# mikroe-adapter.net
KiCad netlist of a schematic drawn in EAGLE
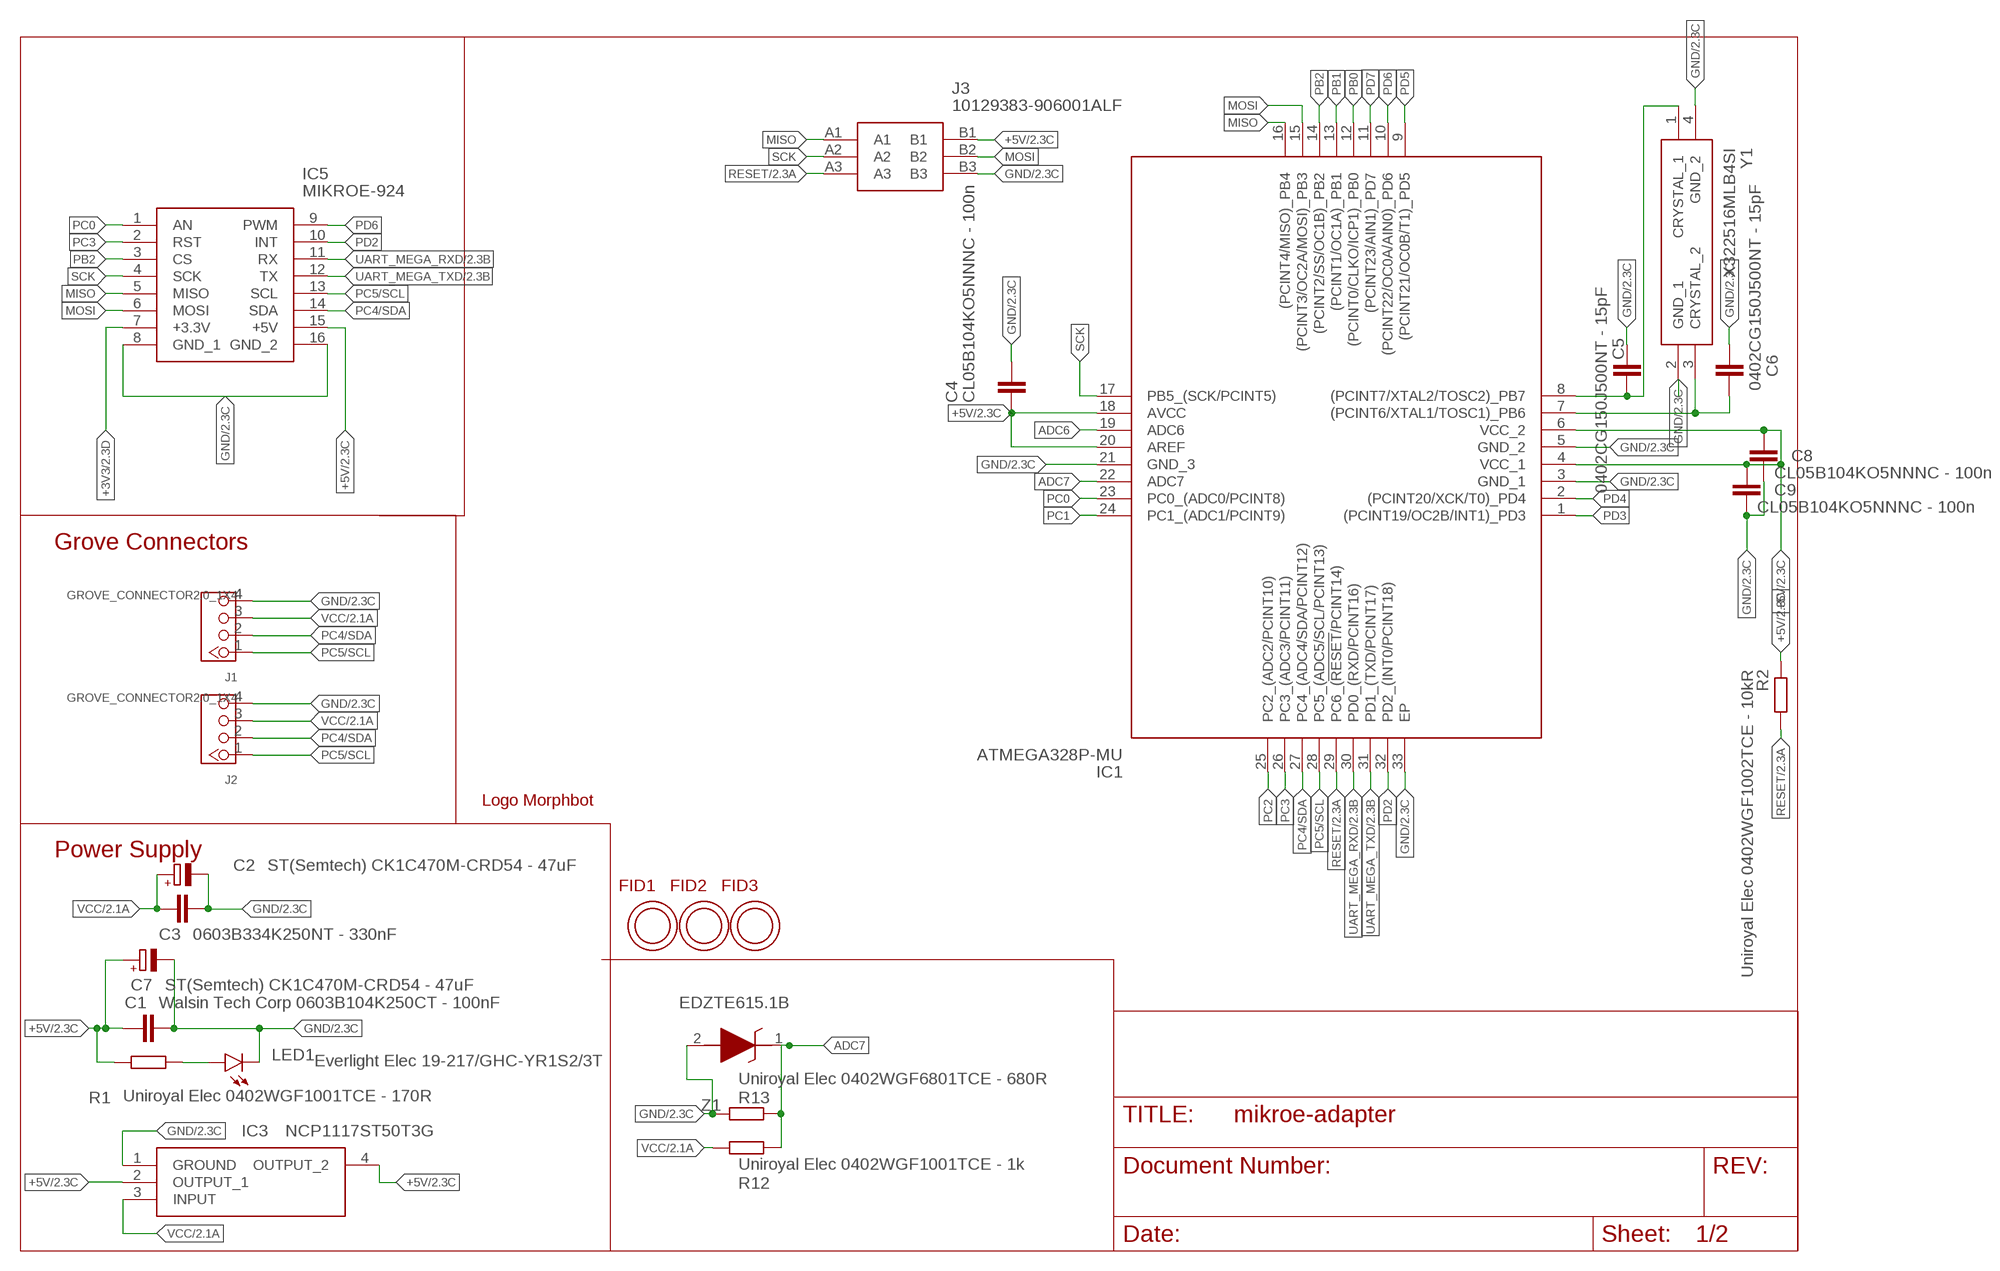
[diagram p0: schematic, sheet 1]
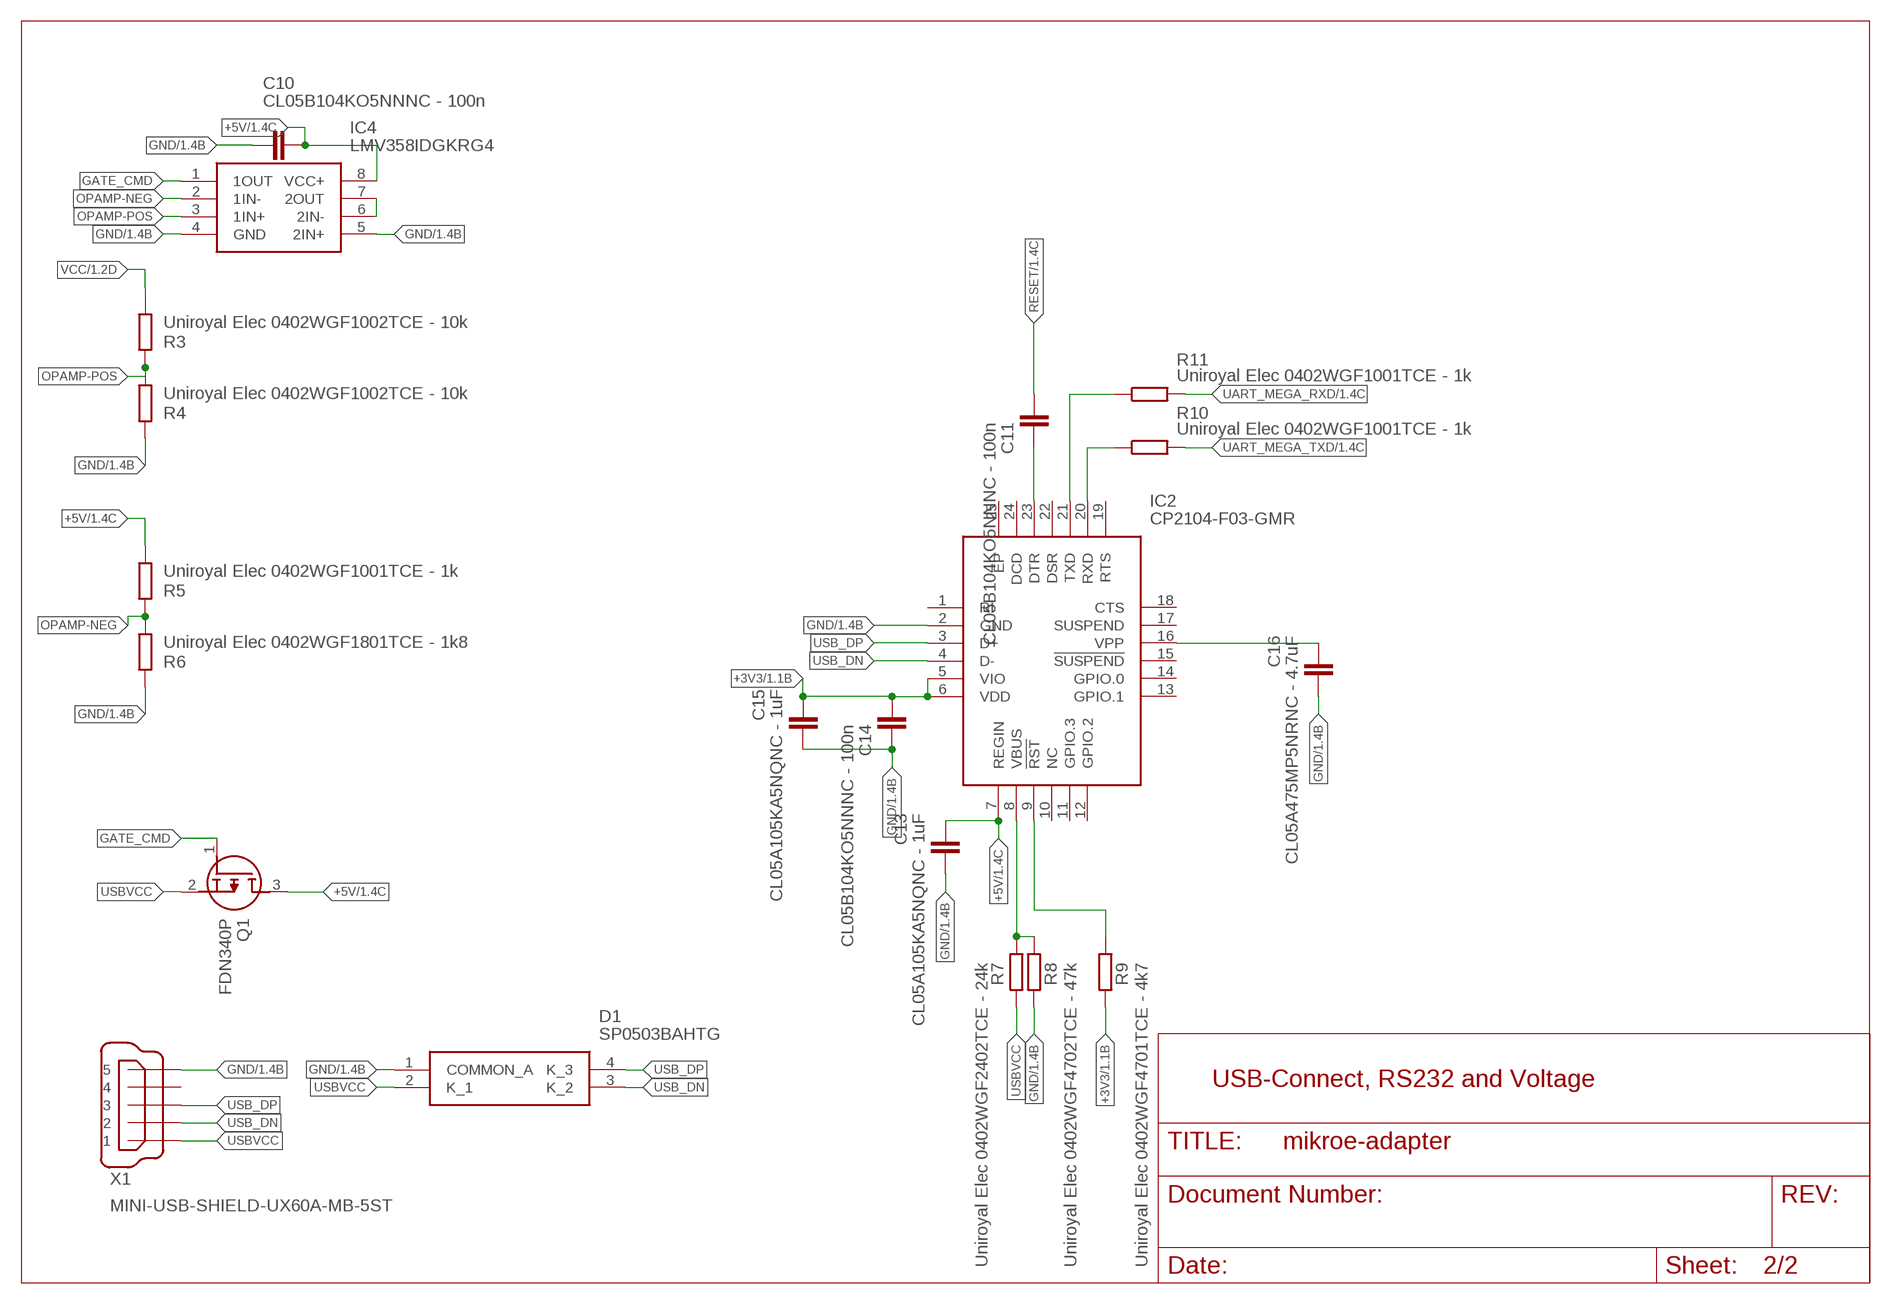
[diagram p1: schematic, sheet 2]

(export (version "E")
  (design (tool "Eeschema 10.0.6"))
  (components
    (comp (ref "C1")
      (value "Walsin Tech Corp 0603B104K250CT - 100nF")
      (footprint "eagle-import:C0603")
      (libsource (lib "eagle-import") (part "C-EUC0603"))
    )
    (comp (ref "C2")
      (value "ST(Semtech) CK1C470M-CRD54 - 47uF")
      (footprint "eagle-import:PANASONIC_C")
      (libsource (lib "eagle-import") (part "CPOL-EUC"))
    )
    (comp (ref "C3")
      (value "0603B334K250NT - 330nF")
      (footprint "eagle-import:C0603")
      (libsource (lib "eagle-import") (part "C-EUC0603"))
    )
    (comp (ref "C4")
      (value "CL05B104KO5NNNC - 100n")
      (footprint "eagle-import:C0402")
      (libsource (lib "eagle-import") (part "C-EUC0402"))
    )
    (comp (ref "C5")
      (value "0402CG150J500NT - 15pF")
      (footprint "eagle-import:C0402")
      (libsource (lib "eagle-import") (part "C-EUC0402"))
    )
    (comp (ref "C6")
      (value "0402CG150J500NT - 15pF")
      (footprint "eagle-import:C0402")
      (libsource (lib "eagle-import") (part "C-EUC0402"))
    )
    (comp (ref "C7")
      (value "ST(Semtech) CK1C470M-CRD54 - 47uF")
      (footprint "eagle-import:PANASONIC_C")
      (libsource (lib "eagle-import") (part "CPOL-EUC"))
    )
    (comp (ref "C8")
      (value "CL05B104KO5NNNC - 100n")
      (footprint "eagle-import:C0402")
      (libsource (lib "eagle-import") (part "C-EUC0402"))
    )
    (comp (ref "C9")
      (value "CL05B104KO5NNNC - 100n")
      (footprint "eagle-import:C0402")
      (libsource (lib "eagle-import") (part "C-EUC0402"))
    )
    (comp (ref "FID1")
      (value "OPEN-PNP-FIDUCIAL")
      (footprint "eagle-import:OPEN-PNP-FIDUCIAL")
      (libsource (lib "eagle-import") (part "OPEN-PNP-FIDUCIAL"))
    )
    (comp (ref "FID2")
      (value "OPEN-PNP-FIDUCIAL")
      (footprint "eagle-import:OPEN-PNP-FIDUCIAL")
      (libsource (lib "eagle-import") (part "OPEN-PNP-FIDUCIAL"))
    )
    (comp (ref "FID3")
      (value "OPEN-PNP-FIDUCIAL")
      (footprint "eagle-import:OPEN-PNP-FIDUCIAL")
      (libsource (lib "eagle-import") (part "OPEN-PNP-FIDUCIAL"))
    )
    (comp (ref "IC1")
      (value "ATMEGA328P-MU")
      (footprint "eagle-import:QFN50P500X500X100-33N")
      (fields (field (name "MOUSER_PART_NUMBER") "556-ATMEGA328P-MU"))
      (libsource (lib "eagle-import") (part "ATMEGA328P-MU"))
    )
    (comp (ref "IC3")
      (value "NCP1117ST50T3G")
      (footprint "eagle-import:SOT230P700X180-4N")
      (fields (field (name "MOUSER_PART_NUMBER") "863-NCP1117ST50T3G"))
      (libsource (lib "eagle-import") (part "NCP1117ST50T3G"))
    )
    (comp (ref "IC5")
      (value "MIKROE-924")
      (footprint "eagle-import:MIKROE924")
      (fields (field (name "MOUSER_PART_NUMBER") "932-MIKROE-924"))
      (libsource (lib "eagle-import") (part "MIKROE-924"))
    )
    (comp (ref "J1")
      (value "GROVE_CONNECTOR2.0_1X4")
      (footprint "eagle-import:2.0_1X4_STRAIGHT")
      (libsource (lib "eagle-import") (part "GROVE_CONNECTOR2.0_1X4"))
    )
    (comp (ref "J2")
      (value "GROVE_CONNECTOR2.0_1X4")
      (footprint "eagle-import:2.0_1X4_STRAIGHT")
      (libsource (lib "eagle-import") (part "GROVE_CONNECTOR2.0_1X4"))
    )
    (comp (ref "J3")
      (value "10129383-906001ALF")
      (footprint "eagle-import:10129383906001ALF")
      (fields (field (name "MOUSER_PART_NUMBER") "649-1012938390601ALF"))
      (libsource (lib "eagle-import") (part "10129383-906001ALF"))
    )
    (comp (ref "LED1")
      (value "Everlight Elec 19-217/GHC-YR1S2/3T")
      (footprint "eagle-import:CHIPLED_0603")
      (libsource (lib "eagle-import") (part "LEDCHIPLED_0603"))
    )
    (comp (ref "R1")
      (value "Uniroyal Elec 0402WGF1001TCE - 170R")
      (footprint "eagle-import:R0402")
      (libsource (lib "eagle-import") (part "R-EU_R0402"))
    )
    (comp (ref "R2")
      (value "Uniroyal Elec 0402WGF1002TCE - 10kR")
      (footprint "eagle-import:R0402")
      (libsource (lib "eagle-import") (part "R-EU_R0402"))
    )
    (comp (ref "R12")
      (value "Uniroyal Elec 0402WGF1001TCE - 1k")
      (footprint "eagle-import:R0402")
      (libsource (lib "eagle-import") (part "R-EU_R0402"))
    )
    (comp (ref "R13")
      (value "Uniroyal Elec 0402WGF6801TCE - 680R")
      (footprint "eagle-import:R0402")
      (libsource (lib "eagle-import") (part "R-EU_R0402"))
    )
    (comp (ref "U$1")
      (value "LOGO_MORPHBOT5MM")
      (footprint "eagle-import:LOGO_MORPHBOT")
      (libsource (lib "eagle-import") (part "LOGO_MORPHBOT5MM"))
    )
    (comp (ref "Y1")
      (value "X322516MLB4SI")
      (footprint "eagle-import:X322516MLB4SI")
      (libsource (lib "eagle-import") (part "X322516MLB4SI"))
    )
    (comp (ref "Z1")
      (value "EDZTE615.1B")
      (footprint "eagle-import:EMD2")
      (fields (field (name "MOUSER_PART_NUMBER") "755-EDZTE615.1B"))
      (libsource (lib "eagle-import") (part "EDZTE615.1B"))
    )
    (comp (ref "C10")
      (value "CL05B104KO5NNNC - 100n")
      (footprint "eagle-import:C0402")
      (libsource (lib "eagle-import") (part "C-EUC0402"))
    )
    (comp (ref "C11")
      (value "CL05B104KO5NNNC - 100n")
      (footprint "eagle-import:C0402")
      (libsource (lib "eagle-import") (part "C-EUC0402"))
    )
    (comp (ref "C13")
      (value "CL05A105KA5NQNC - 1uF")
      (footprint "eagle-import:C0402")
      (libsource (lib "eagle-import") (part "C-EUC0402"))
    )
    (comp (ref "C14")
      (value "CL05B104KO5NNNC - 100n")
      (footprint "eagle-import:C0402")
      (libsource (lib "eagle-import") (part "C-EUC0402"))
    )
    (comp (ref "C15")
      (value "CL05A105KA5NQNC - 1uF")
      (footprint "eagle-import:C0402")
      (libsource (lib "eagle-import") (part "C-EUC0402"))
    )
    (comp (ref "C16")
      (value "CL05A475MP5NRNC - 4.7uF")
      (footprint "eagle-import:C0402")
      (libsource (lib "eagle-import") (part "C-EUC0402"))
    )
    (comp (ref "D1")
      (value "SP0503BAHTG")
      (footprint "eagle-import:SP0503BAHTG")
      (fields (field (name "MOUSER_PART_NUMBER") "576-SP0503BAHTG"))
      (libsource (lib "eagle-import") (part "SP0503BAHTG"))
    )
    (comp (ref "IC2")
      (value "CP2104-F03-GMR")
      (footprint "eagle-import:QFN50P400X400X80-25N")
      (fields (field (name "MOUSER_PART_NUMBER") "634-CP2104-F03-GMR"))
      (libsource (lib "eagle-import") (part "CP2104-F03-GMR"))
    )
    (comp (ref "IC4")
      (value "LMV358IDGKRG4")
      (footprint "eagle-import:SOP65P490X110-8N")
      (fields (field (name "MOUSER_PART_NUMBER") "595-LMV358IDGKRG4"))
      (libsource (lib "eagle-import") (part "LMV358IDGKRG4"))
    )
    (comp (ref "Q1")
      (value "FDN340P")
      (footprint "eagle-import:SOT95P237X112-3N")
      (fields (field (name "MOUSER_PART_NUMBER") "512-FDN340P"))
      (libsource (lib "eagle-import") (part "FDN340P"))
    )
    (comp (ref "R3")
      (value "Uniroyal Elec 0402WGF1002TCE - 10k")
      (footprint "eagle-import:R0402")
      (libsource (lib "eagle-import") (part "R-EU_R0402"))
    )
    (comp (ref "R4")
      (value "Uniroyal Elec 0402WGF1002TCE - 10k")
      (footprint "eagle-import:R0402")
      (libsource (lib "eagle-import") (part "R-EU_R0402"))
    )
    (comp (ref "R5")
      (value "Uniroyal Elec 0402WGF1001TCE - 1k")
      (footprint "eagle-import:R0402")
      (libsource (lib "eagle-import") (part "R-EU_R0402"))
    )
    (comp (ref "R6")
      (value "Uniroyal Elec 0402WGF1801TCE - 1k8")
      (footprint "eagle-import:R0402")
      (libsource (lib "eagle-import") (part "R-EU_R0402"))
    )
    (comp (ref "R7")
      (value "Uniroyal Elec 0402WGF2402TCE - 24k")
      (footprint "eagle-import:R0402")
      (libsource (lib "eagle-import") (part "R-EU_R0402"))
    )
    (comp (ref "R8")
      (value "Uniroyal Elec 0402WGF4702TCE - 47k")
      (footprint "eagle-import:R0402")
      (libsource (lib "eagle-import") (part "R-EU_R0402"))
    )
    (comp (ref "R9")
      (value "Uniroyal Elec 0402WGF4701TCE - 4k7")
      (footprint "eagle-import:R0402")
      (libsource (lib "eagle-import") (part "R-EU_R0402"))
    )
    (comp (ref "R10")
      (value "Uniroyal Elec 0402WGF1001TCE - 1k")
      (footprint "eagle-import:R0402")
      (libsource (lib "eagle-import") (part "R-EU_R0402"))
    )
    (comp (ref "R11")
      (value "Uniroyal Elec 0402WGF1001TCE - 1k")
      (footprint "eagle-import:R0402")
      (libsource (lib "eagle-import") (part "R-EU_R0402"))
    )
    (comp (ref "X1")
      (value "MINI-USB-SHIELD-UX60A-MB-5ST")
      (footprint "eagle-import:UX60A-MB-5ST")
      (libsource (lib "eagle-import") (part "MINI-USB-SHIELD-UX60A-MB-5ST"))
    )
  )
  (nets
    (net (code "1") (name "+3V3") (class "Default")
      (node (ref "C14") (pin "2") (pinfunction "2_2") (pintype "passive"))
      (node (ref "C15") (pin "2") (pinfunction "2_2") (pintype "passive"))
      (node (ref "IC2") (pin "5") (pinfunction "VIO_5") (pintype "bidirectional"))
      (node (ref "IC2") (pin "6") (pinfunction "VDD_6") (pintype "bidirectional"))
      (node (ref "IC5") (pin "7") (pinfunction "+3.3V_7") (pintype "bidirectional"))
      (node (ref "R9") (pin "2") (pinfunction "2_2") (pintype "passive"))
    )
    (net (code "2") (name "+5V") (class "Default")
      (node (ref "C1") (pin "1") (pinfunction "1_1") (pintype "passive"))
      (node (ref "C10") (pin "2") (pinfunction "2_2") (pintype "passive"))
      (node (ref "C13") (pin "2") (pinfunction "2_2") (pintype "passive"))
      (node (ref "C4") (pin "1") (pinfunction "1_1") (pintype "passive"))
      (node (ref "C7") (pin "+") (pinfunction "+_+") (pintype "passive"))
      (node (ref "C8") (pin "2") (pinfunction "2_2") (pintype "passive"))
      (node (ref "C9") (pin "2") (pinfunction "2_2") (pintype "passive"))
      (node (ref "IC1") (pin "18") (pinfunction "AVCC_18") (pintype "bidirectional"))
      (node (ref "IC1") (pin "20") (pinfunction "AREF_20") (pintype "bidirectional"))
      (node (ref "IC1") (pin "4") (pinfunction "VCC_1_4") (pintype "bidirectional"))
      (node (ref "IC1") (pin "6") (pinfunction "VCC_2_6") (pintype "bidirectional"))
      (node (ref "IC2") (pin "7") (pinfunction "REGIN_7") (pintype "bidirectional"))
      (node (ref "IC3") (pin "2") (pinfunction "OUTPUT_1_2") (pintype "bidirectional"))
      (node (ref "IC3") (pin "4") (pinfunction "OUTPUT_2_4") (pintype "bidirectional"))
      (node (ref "IC4") (pin "8") (pinfunction "VCC+_8") (pintype "bidirectional"))
      (node (ref "IC5") (pin "15") (pinfunction "+5V_15") (pintype "bidirectional"))
      (node (ref "J3") (pin "B1") (pinfunction "B1_B1") (pintype "bidirectional"))
      (node (ref "Q1") (pin "3") (pinfunction "D_3") (pintype "bidirectional"))
      (node (ref "R1") (pin "2") (pinfunction "2_2") (pintype "passive"))
      (node (ref "R2") (pin "2") (pinfunction "2_2") (pintype "passive"))
      (node (ref "R5") (pin "1") (pinfunction "1_1") (pintype "passive"))
    )
    (net (code "3") (name "ADC6") (class "Default")
      (node (ref "IC1") (pin "19") (pinfunction "ADC6_19") (pintype "bidirectional"))
    )
    (net (code "4") (name "ADC7") (class "Default")
      (node (ref "IC1") (pin "22") (pinfunction "ADC7_22") (pintype "bidirectional"))
      (node (ref "R12") (pin "1") (pinfunction "1_1") (pintype "passive"))
      (node (ref "R13") (pin "2") (pinfunction "2_2") (pintype "passive"))
      (node (ref "Z1") (pin "1") (pinfunction "K_1") (pintype "bidirectional"))
    )
    (net (code "5") (name "GATE_CMD") (class "Default")
      (node (ref "IC4") (pin "1") (pinfunction "1OUT_1") (pintype "bidirectional"))
      (node (ref "Q1") (pin "1") (pinfunction "G_1") (pintype "bidirectional"))
    )
    (net (code "6") (name "GND") (class "Default")
      (node (ref "C1") (pin "2") (pinfunction "2_2") (pintype "passive"))
      (node (ref "C10") (pin "1") (pinfunction "1_1") (pintype "passive"))
      (node (ref "C13") (pin "1") (pinfunction "1_1") (pintype "passive"))
      (node (ref "C14") (pin "1") (pinfunction "1_1") (pintype "passive"))
      (node (ref "C15") (pin "1") (pinfunction "1_1") (pintype "passive"))
      (node (ref "C16") (pin "1") (pinfunction "1_1") (pintype "passive"))
      (node (ref "C2") (pin "-") (pinfunction "-_-") (pintype "passive"))
      (node (ref "C3") (pin "1") (pinfunction "1_1") (pintype "passive"))
      (node (ref "C4") (pin "2") (pinfunction "2_2") (pintype "passive"))
      (node (ref "C5") (pin "1") (pinfunction "1_1") (pintype "passive"))
      (node (ref "C6") (pin "1") (pinfunction "1_1") (pintype "passive"))
      (node (ref "C7") (pin "-") (pinfunction "-_-") (pintype "passive"))
      (node (ref "C8") (pin "1") (pinfunction "1_1") (pintype "passive"))
      (node (ref "C9") (pin "1") (pinfunction "1_1") (pintype "passive"))
      (node (ref "D1") (pin "1") (pinfunction "COMMON_A_1") (pintype "bidirectional"))
      (node (ref "IC1") (pin "21") (pinfunction "GND_3_21") (pintype "bidirectional"))
      (node (ref "IC1") (pin "3") (pinfunction "GND_1_3") (pintype "bidirectional"))
      (node (ref "IC1") (pin "33") (pinfunction "EP_33") (pintype "bidirectional"))
      (node (ref "IC1") (pin "5") (pinfunction "GND_2_5") (pintype "bidirectional"))
      (node (ref "IC2") (pin "2") (pinfunction "GND_2") (pintype "bidirectional"))
      (node (ref "IC3") (pin "1") (pinfunction "GROUND_1") (pintype "bidirectional"))
      (node (ref "IC4") (pin "4") (pinfunction "GND_4") (pintype "bidirectional"))
      (node (ref "IC4") (pin "5") (pinfunction "2IN+_5") (pintype "bidirectional"))
      (node (ref "IC5") (pin "16") (pinfunction "GND_2_16") (pintype "bidirectional"))
      (node (ref "IC5") (pin "8") (pinfunction "GND_1_8") (pintype "bidirectional"))
      (node (ref "J1") (pin "4") (pinfunction "4_4") (pintype "bidirectional"))
      (node (ref "J2") (pin "4") (pinfunction "4_4") (pintype "bidirectional"))
      (node (ref "J3") (pin "B3") (pinfunction "B3_B3") (pintype "bidirectional"))
      (node (ref "LED1") (pin "C") (pinfunction "C_C") (pintype "passive"))
      (node (ref "R13") (pin "1") (pinfunction "1_1") (pintype "passive"))
      (node (ref "R4") (pin "2") (pinfunction "2_2") (pintype "passive"))
      (node (ref "R6") (pin "2") (pinfunction "2_2") (pintype "passive"))
      (node (ref "R8") (pin "2") (pinfunction "2_2") (pintype "passive"))
      (node (ref "X1") (pin "5") (pinfunction "5_5") (pintype "input"))
      (node (ref "Y1") (pin "2") (pinfunction "GND_1_2") (pintype "bidirectional"))
      (node (ref "Y1") (pin "4") (pinfunction "GND_2_4") (pintype "bidirectional"))
      (node (ref "Z1") (pin "2") (pinfunction "A_2") (pintype "bidirectional"))
    )
    (net (code "7") (name "MISO") (class "Default")
      (node (ref "IC1") (pin "16") (pinfunction "(PCINT4/MISO)_PB4_16") (pintype "bidirectional"))
      (node (ref "IC5") (pin "5") (pinfunction "MISO_5") (pintype "bidirectional"))
      (node (ref "J3") (pin "A1") (pinfunction "A1_A1") (pintype "bidirectional"))
    )
    (net (code "8") (name "MOSI") (class "Default")
      (node (ref "IC1") (pin "15") (pinfunction "(PCINT3/OC2A/MOSI)_PB3_15") (pintype "bidirectional"))
      (node (ref "IC5") (pin "6") (pinfunction "MOSI_6") (pintype "bidirectional"))
      (node (ref "J3") (pin "B2") (pinfunction "B2_B2") (pintype "bidirectional"))
    )
    (net (code "9") (name "Net-(IC1-(PCINT6{slash}XTAL1{slash}TOSC1)_PB6)") (class "Default")
      (node (ref "C6") (pin "2") (pinfunction "2_2") (pintype "passive"))
      (node (ref "IC1") (pin "7") (pinfunction "(PCINT6/XTAL1/TOSC1)_PB6_7") (pintype "bidirectional"))
      (node (ref "Y1") (pin "3") (pinfunction "CRYSTAL_2_3") (pintype "bidirectional"))
    )
    (net (code "10") (name "Net-(IC1-(PCINT7{slash}XTAL2{slash}TOSC2)_PB7)") (class "Default")
      (node (ref "C5") (pin "2") (pinfunction "2_2") (pintype "passive"))
      (node (ref "IC1") (pin "8") (pinfunction "(PCINT7/XTAL2/TOSC2)_PB7_8") (pintype "bidirectional"))
      (node (ref "Y1") (pin "1") (pinfunction "CRYSTAL_1_1") (pintype "bidirectional"))
    )
    (net (code "11") (name "Net-(IC2-DTR)") (class "Default")
      (node (ref "C11") (pin "1") (pinfunction "1_1") (pintype "passive"))
      (node (ref "IC2") (pin "23") (pinfunction "DTR_23") (pintype "bidirectional"))
    )
    (net (code "12") (name "Net-(IC2-RXD)") (class "Default")
      (node (ref "IC2") (pin "20") (pinfunction "RXD_20") (pintype "bidirectional"))
      (node (ref "R10") (pin "1") (pinfunction "1_1") (pintype "passive"))
    )
    (net (code "13") (name "Net-(IC2-TXD)") (class "Default")
      (node (ref "IC2") (pin "21") (pinfunction "TXD_21") (pintype "bidirectional"))
      (node (ref "R11") (pin "1") (pinfunction "1_1") (pintype "passive"))
    )
    (net (code "14") (name "Net-(IC2-VBUS)") (class "Default")
      (node (ref "IC2") (pin "8") (pinfunction "VBUS_8") (pintype "bidirectional"))
      (node (ref "R7") (pin "1") (pinfunction "1_1") (pintype "passive"))
      (node (ref "R8") (pin "1") (pinfunction "1_1") (pintype "passive"))
    )
    (net (code "15") (name "Net-(IC2-VPP)") (class "Default")
      (node (ref "C16") (pin "2") (pinfunction "2_2") (pintype "passive"))
      (node (ref "IC2") (pin "16") (pinfunction "VPP_16") (pintype "bidirectional"))
    )
    (net (code "16") (name "Net-(IC2-~{RST})") (class "Default")
      (node (ref "IC2") (pin "9") (pinfunction "~{RST}_9") (pintype "bidirectional"))
      (node (ref "R9") (pin "1") (pinfunction "1_1") (pintype "passive"))
    )
    (net (code "17") (name "Net-(IC4-2IN-)") (class "Default")
      (node (ref "IC4") (pin "6") (pinfunction "2IN-_6") (pintype "bidirectional"))
      (node (ref "IC4") (pin "7") (pinfunction "2OUT_7") (pintype "bidirectional"))
    )
    (net (code "18") (name "Net-(LED1-PadA)") (class "Default")
      (node (ref "LED1") (pin "A") (pinfunction "A_A") (pintype "passive"))
      (node (ref "R1") (pin "1") (pinfunction "1_1") (pintype "passive"))
    )
    (net (code "19") (name "OPAMP-NEG") (class "Default")
      (node (ref "IC4") (pin "2") (pinfunction "1IN-_2") (pintype "bidirectional"))
      (node (ref "R5") (pin "2") (pinfunction "2_2") (pintype "passive"))
      (node (ref "R6") (pin "1") (pinfunction "1_1") (pintype "passive"))
    )
    (net (code "20") (name "OPAMP-POS") (class "Default")
      (node (ref "IC4") (pin "3") (pinfunction "1IN+_3") (pintype "bidirectional"))
      (node (ref "R3") (pin "2") (pinfunction "2_2") (pintype "passive"))
      (node (ref "R4") (pin "1") (pinfunction "1_1") (pintype "passive"))
    )
    (net (code "21") (name "PB0") (class "Default")
      (node (ref "IC1") (pin "12") (pinfunction "(PCINT0/CLKO/ICP1)_PB0_12") (pintype "bidirectional"))
    )
    (net (code "22") (name "PB1") (class "Default")
      (node (ref "IC1") (pin "13") (pinfunction "(PCINT1/OC1A)_PB1_13") (pintype "bidirectional"))
    )
    (net (code "23") (name "PB2") (class "Default")
      (node (ref "IC1") (pin "14") (pinfunction "(PCINT2/SS/OC1B)_PB2_14") (pintype "bidirectional"))
      (node (ref "IC5") (pin "3") (pinfunction "CS_3") (pintype "bidirectional"))
    )
    (net (code "24") (name "PC0") (class "Default")
      (node (ref "IC1") (pin "23") (pinfunction "PC0_(ADC0/PCINT8)_23") (pintype "bidirectional"))
      (node (ref "IC5") (pin "1") (pinfunction "AN_1") (pintype "bidirectional"))
    )
    (net (code "25") (name "PC1") (class "Default")
      (node (ref "IC1") (pin "24") (pinfunction "PC1_(ADC1/PCINT9)_24") (pintype "bidirectional"))
    )
    (net (code "26") (name "PC2") (class "Default")
      (node (ref "IC1") (pin "25") (pinfunction "PC2_(ADC2/PCINT10)_25") (pintype "bidirectional"))
    )
    (net (code "27") (name "PC3") (class "Default")
      (node (ref "IC1") (pin "26") (pinfunction "PC3_(ADC3/PCINT11)_26") (pintype "bidirectional"))
      (node (ref "IC5") (pin "2") (pinfunction "RST_2") (pintype "bidirectional"))
    )
    (net (code "28") (name "PC4{slash}SDA") (class "Default")
      (node (ref "IC1") (pin "27") (pinfunction "PC4_(ADC4/SDA/PCINT12)_27") (pintype "bidirectional"))
      (node (ref "IC5") (pin "14") (pinfunction "SDA_14") (pintype "bidirectional"))
      (node (ref "J1") (pin "2") (pinfunction "2_2") (pintype "bidirectional"))
      (node (ref "J2") (pin "2") (pinfunction "2_2") (pintype "bidirectional"))
    )
    (net (code "29") (name "PC5{slash}SCL") (class "Default")
      (node (ref "IC1") (pin "28") (pinfunction "PC5_(ADC5/SCL/PCINT13)_28") (pintype "bidirectional"))
      (node (ref "IC5") (pin "13") (pinfunction "SCL_13") (pintype "bidirectional"))
      (node (ref "J1") (pin "1") (pinfunction "1_1") (pintype "bidirectional"))
      (node (ref "J2") (pin "1") (pinfunction "1_1") (pintype "bidirectional"))
    )
    (net (code "30") (name "PD2") (class "Default")
      (node (ref "IC1") (pin "32") (pinfunction "PD2_(INT0/PCINT18)_32") (pintype "bidirectional"))
      (node (ref "IC5") (pin "10") (pinfunction "INT_10") (pintype "bidirectional"))
    )
    (net (code "31") (name "PD3") (class "Default")
      (node (ref "IC1") (pin "1") (pinfunction "(PCINT19/OC2B/INT1)_PD3_1") (pintype "bidirectional"))
    )
    (net (code "32") (name "PD4") (class "Default")
      (node (ref "IC1") (pin "2") (pinfunction "(PCINT20/XCK/T0)_PD4_2") (pintype "bidirectional"))
    )
    (net (code "33") (name "PD5") (class "Default")
      (node (ref "IC1") (pin "9") (pinfunction "(PCINT21/OC0B/T1)_PD5_9") (pintype "bidirectional"))
    )
    (net (code "34") (name "PD6") (class "Default")
      (node (ref "IC1") (pin "10") (pinfunction "(PCINT22/OC0A/AIN0)_PD6_10") (pintype "bidirectional"))
      (node (ref "IC5") (pin "9") (pinfunction "PWM_9") (pintype "bidirectional"))
    )
    (net (code "35") (name "PD7") (class "Default")
      (node (ref "IC1") (pin "11") (pinfunction "(PCINT23/AIN1)_PD7_11") (pintype "bidirectional"))
    )
    (net (code "36") (name "RESET") (class "Default")
      (node (ref "C11") (pin "2") (pinfunction "2_2") (pintype "passive"))
      (node (ref "IC1") (pin "29") (pinfunction "PC6_(~{RESET}/PCINT14)_29") (pintype "bidirectional"))
      (node (ref "J3") (pin "A3") (pinfunction "A3_A3") (pintype "bidirectional"))
      (node (ref "R2") (pin "1") (pinfunction "1_1") (pintype "passive"))
    )
    (net (code "37") (name "SCK") (class "Default")
      (node (ref "IC1") (pin "17") (pinfunction "PB5_(SCK/PCINT5)_17") (pintype "bidirectional"))
      (node (ref "IC5") (pin "4") (pinfunction "SCK_4") (pintype "bidirectional"))
      (node (ref "J3") (pin "A2") (pinfunction "A2_A2") (pintype "bidirectional"))
    )
    (net (code "38") (name "UART_MEGA_RXD") (class "Default")
      (node (ref "IC1") (pin "30") (pinfunction "PD0_(RXD/PCINT16)_30") (pintype "bidirectional"))
      (node (ref "IC5") (pin "11") (pinfunction "RX_11") (pintype "bidirectional"))
      (node (ref "R11") (pin "2") (pinfunction "2_2") (pintype "passive"))
    )
    (net (code "39") (name "UART_MEGA_TXD") (class "Default")
      (node (ref "IC1") (pin "31") (pinfunction "PD1_(TXD/PCINT17)_31") (pintype "bidirectional"))
      (node (ref "IC5") (pin "12") (pinfunction "TX_12") (pintype "bidirectional"))
      (node (ref "R10") (pin "2") (pinfunction "2_2") (pintype "passive"))
    )
    (net (code "40") (name "USBVCC") (class "Default")
      (node (ref "D1") (pin "2") (pinfunction "K_1_2") (pintype "bidirectional"))
      (node (ref "Q1") (pin "2") (pinfunction "S_2") (pintype "bidirectional"))
      (node (ref "R7") (pin "2") (pinfunction "2_2") (pintype "passive"))
      (node (ref "X1") (pin "1") (pinfunction "1_1") (pintype "input"))
    )
    (net (code "41") (name "USB_DN") (class "Default")
      (node (ref "D1") (pin "3") (pinfunction "K_2_3") (pintype "bidirectional"))
      (node (ref "IC2") (pin "4") (pinfunction "D-_4") (pintype "bidirectional"))
      (node (ref "X1") (pin "2") (pinfunction "2_2") (pintype "input"))
    )
    (net (code "42") (name "USB_DP") (class "Default")
      (node (ref "D1") (pin "4") (pinfunction "K_3_4") (pintype "bidirectional"))
      (node (ref "IC2") (pin "3") (pinfunction "D+_3") (pintype "bidirectional"))
      (node (ref "X1") (pin "3") (pinfunction "3_3") (pintype "input"))
    )
    (net (code "43") (name "VCC") (class "Default")
      (node (ref "C2") (pin "+") (pinfunction "+_+") (pintype "passive"))
      (node (ref "C3") (pin "2") (pinfunction "2_2") (pintype "passive"))
      (node (ref "IC3") (pin "3") (pinfunction "INPUT_3") (pintype "bidirectional"))
      (node (ref "J1") (pin "3") (pinfunction "3_3") (pintype "bidirectional"))
      (node (ref "J2") (pin "3") (pinfunction "3_3") (pintype "bidirectional"))
      (node (ref "R12") (pin "2") (pinfunction "2_2") (pintype "passive"))
      (node (ref "R3") (pin "1") (pinfunction "1_1") (pintype "passive"))
    )
    (net (code "44") (name "unconnected-(IC2-CTS-Pad18)") (class "Default")
      (node (ref "IC2") (pin "18") (pinfunction "CTS_18") (pintype "bidirectional"))
    )
    (net (code "45") (name "unconnected-(IC2-DCD-Pad24)") (class "Default")
      (node (ref "IC2") (pin "24") (pinfunction "DCD_24") (pintype "bidirectional"))
    )
    (net (code "46") (name "unconnected-(IC2-DSR-Pad22)") (class "Default")
      (node (ref "IC2") (pin "22") (pinfunction "DSR_22") (pintype "bidirectional"))
    )
    (net (code "47") (name "unconnected-(IC2-EP-Pad25)") (class "Default")
      (node (ref "IC2") (pin "25") (pinfunction "EP_25") (pintype "bidirectional"))
    )
    (net (code "48") (name "unconnected-(IC2-GPIO.0-Pad14)") (class "Default")
      (node (ref "IC2") (pin "14") (pinfunction "GPIO.0_14") (pintype "bidirectional"))
    )
    (net (code "49") (name "unconnected-(IC2-GPIO.1-Pad13)") (class "Default")
      (node (ref "IC2") (pin "13") (pinfunction "GPIO.1_13") (pintype "bidirectional"))
    )
    (net (code "50") (name "unconnected-(IC2-GPIO.2-Pad12)") (class "Default")
      (node (ref "IC2") (pin "12") (pinfunction "GPIO.2_12") (pintype "bidirectional"))
    )
    (net (code "51") (name "unconnected-(IC2-GPIO.3-Pad11)") (class "Default")
      (node (ref "IC2") (pin "11") (pinfunction "GPIO.3_11") (pintype "bidirectional"))
    )
    (net (code "52") (name "unconnected-(IC2-NC-Pad10)") (class "Default")
      (node (ref "IC2") (pin "10") (pinfunction "NC_10") (pintype "no_connect"))
    )
    (net (code "53") (name "unconnected-(IC2-RI-Pad1)") (class "Default")
      (node (ref "IC2") (pin "1") (pinfunction "RI_1") (pintype "bidirectional"))
    )
    (net (code "54") (name "unconnected-(IC2-RTS-Pad19)") (class "Default")
      (node (ref "IC2") (pin "19") (pinfunction "RTS_19") (pintype "bidirectional"))
    )
    (net (code "55") (name "unconnected-(IC2-SUSPEND-Pad17)") (class "Default")
      (node (ref "IC2") (pin "17") (pinfunction "SUSPEND_17") (pintype "bidirectional"))
    )
    (net (code "56") (name "unconnected-(IC2-~{SUSPEND}-Pad15)") (class "Default")
      (node (ref "IC2") (pin "15") (pinfunction "~{SUSPEND}_15") (pintype "bidirectional"))
    )
    (net (code "57") (name "unconnected-(X1-Pad4)") (class "Default")
      (node (ref "X1") (pin "4") (pinfunction "4_4") (pintype "input"))
    )
  )
)
